# autonomiczny_odkurzacz_sch.net
KiCad netlist of a schematic drawn in Altium Designer
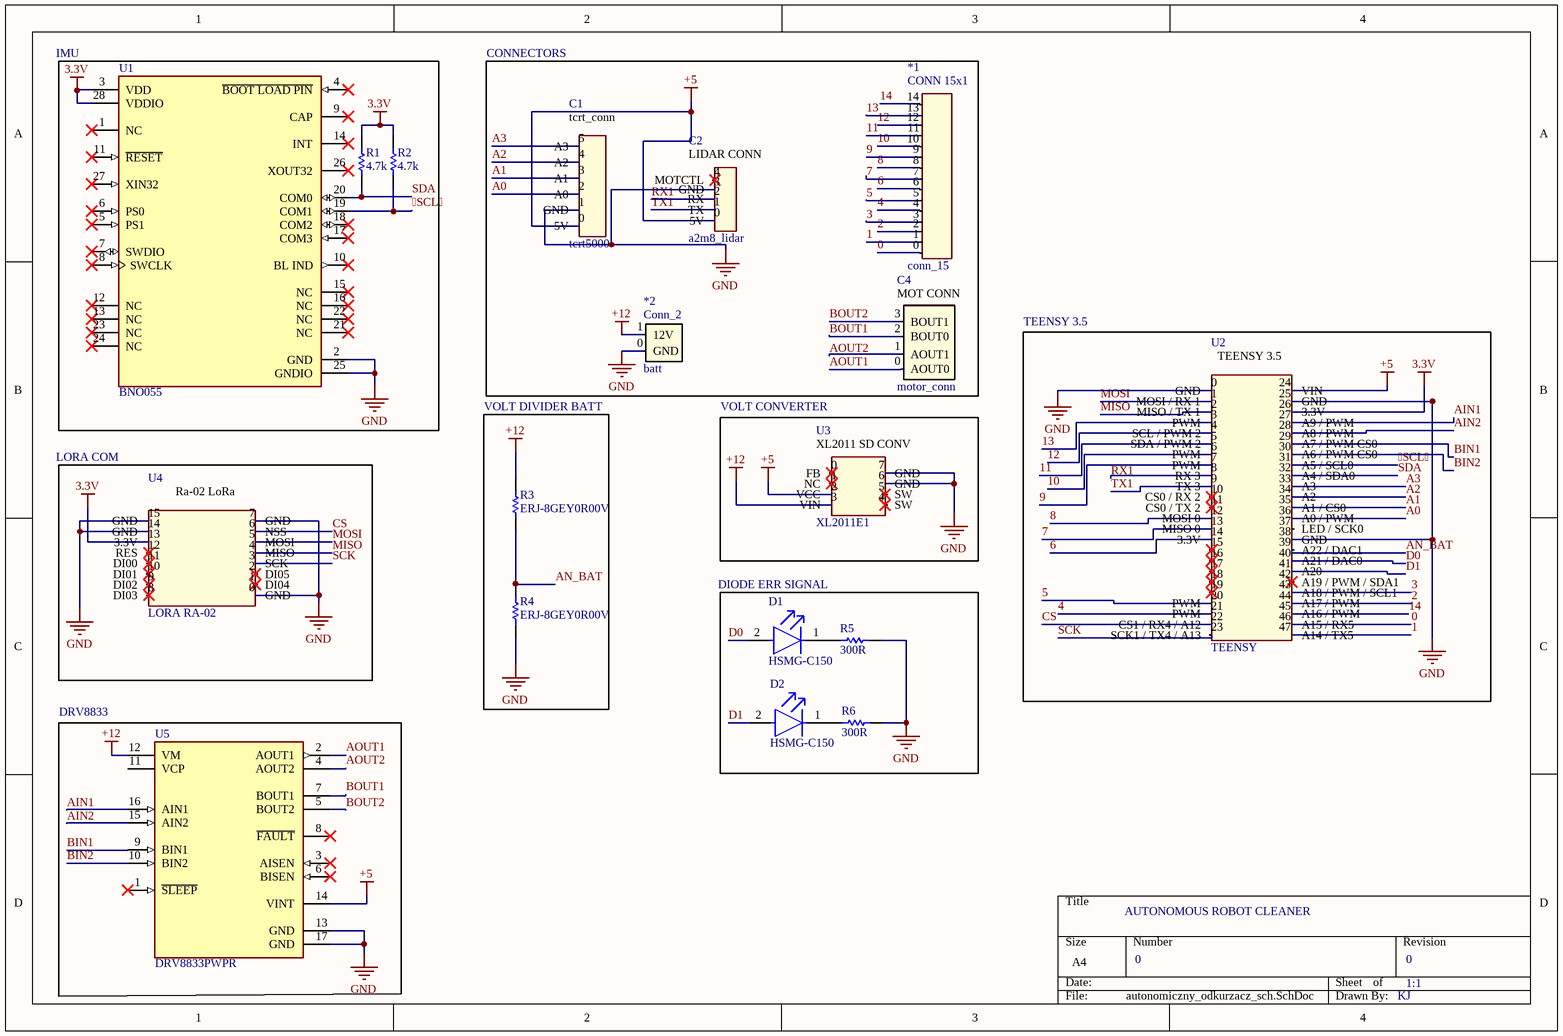
[diagram p0: autonomiczny_odkurzacz_sch.SchDoc]

(export (version "E")
  (design (tool "Eeschema 10.0.6"))
  (components
    (comp (ref "*1")
      (value "conn_15")
      (footprint "PCBComponent_1")
      (libsource (lib "workspace_kj_st") (part "conn_15"))
    )
    (comp (ref "*2") (value "batt") (footprint "conn_2:conn_2") (libsource (lib "MySchLib") (part "conn_2")))
    (comp (ref "C1")
      (value "tcrt5000")
      (footprint "PCBComponent_1")
      (libsource (lib "workspace_kj_st") (part "tcrt"))
    )
    (comp (ref "C2")
      (value "a2m8_lidar")
      (footprint "lidar_pcb:PCBComponent_1")
      (libsource (lib "MySchLib") (part "a2m8_lidar"))
    )
    (comp (ref "C4")
      (value "motor_conn")
      (footprint "PCBComponent_1")
      (libsource (lib "workspace_kj_st") (part "motor_conn"))
    )
    (comp (ref "D1")
      (value "HSMG-C150")
      (footprint "FP-HSMG-C150-MFG")
      (description "LED GREEN DIFFUSED 1206 SMD")
      (fields
        (field (name "MANUFACTURER") "Broadcom")
        (field (name "OCTOPART") "https://octopart.com/hsmg-c150-broadcom-71131304")
      )
      (libsource (lib "Altium Content Vault") (part "8706943c75ba83719d021d2fdc84c58"))
    )
    (comp (ref "D2")
      (value "HSMG-C150")
      (footprint "FP-HSMG-C150-MFG")
      (description "LED GREEN DIFFUSED 1206 SMD")
      (fields
        (field (name "MANUFACTURER") "Broadcom")
        (field (name "OCTOPART") "https://octopart.com/hsmg-c150-broadcom-71131304")
      )
      (libsource (lib "Altium Content Vault") (part "8706943c75ba83719d021d2fdc84c58"))
    )
    (comp (ref "R1")
      (value "4.7k")
      (footprint "RESC3216X70X50NL05T20")
      (fields (field (name "MANUFACTURER") "Panasonic") (field (name "PART NUMBER") "ERJ-8GEY0R00V"))
      (libsource (lib "Altium Content Vault") (part "RES"))
    )
    (comp (ref "R2")
      (value "4.7k")
      (footprint "RESC3216X70X50NL05T20")
      (fields (field (name "MANUFACTURER") "Panasonic") (field (name "PART NUMBER") "ERJ-8GEY0R00V"))
      (libsource (lib "Altium Content Vault") (part "RES"))
    )
    (comp (ref "R3")
      (value "ERJ-8GEY0R00V")
      (footprint "RESC3216X70X50NL05T20")
      (fields (field (name "MANUFACTURER") "Panasonic"))
      (libsource (lib "Altium Content Vault") (part "RES"))
    )
    (comp (ref "R4")
      (value "ERJ-8GEY0R00V")
      (footprint "RESC3216X70X50NL05T20")
      (fields (field (name "MANUFACTURER") "Panasonic"))
      (libsource (lib "Altium Content Vault") (part "RES"))
    )
    (comp (ref "R5")
      (value "300R")
      (footprint "RESC3216X70X50NL05T20")
      (fields (field (name "MANUFACTURER") "Panasonic") (field (name "PART NUMBER") "ERJ-8GEY0R00V"))
      (libsource (lib "Altium Content Vault") (part "RES"))
    )
    (comp (ref "R6")
      (value "300R")
      (footprint "RESC3216X70X50NL05T20")
      (fields (field (name "MANUFACTURER") "Panasonic") (field (name "PART NUMBER") "ERJ-8GEY0R00V"))
      (libsource (lib "Altium Content Vault") (part "RES"))
    )
    (comp (ref "U1")
      (value "BNO055")
      (footprint "FP-BNO055-MFG")
      (description "IMU ACCEL/GYRO/MAG I2C 28LGA")
      (libsource (lib "Altium Content Vault") (part "ba837af00a0b6167256f888b31462b1"))
    )
    (comp (ref "U2")
      (value "TEENSY")
      (footprint "PCBComponent_1")
      (libsource (lib "workspace_kj_st") (part "teensy_3_5"))
    )
    (comp (ref "U3")
      (value "XL2011E1")
      (footprint "PCBComponent_1")
      (libsource (lib "workspace_kj_st") (part "xl2011e1"))
    )
    (comp (ref "U4")
      (value "LORA RA-02")
      (footprint "lora_pcb:PCBComponent_1")
      (libsource (lib "MySchLib") (part "lora_ra02"))
    )
    (comp (ref "U5")
      (value "DRV8833PWPR")
      (footprint "FP-PWP0016C-IPC_A")
      (description "IC MOTOR DRIVER PAR 16HTSSOP")
      (libsource (lib "Altium Content Vault") (part "bca689d78e207bdabf30b9b31c2f798"))
    )
  )
  (nets
    (net (code "1") (name "+5") (class "Default")
      (node (ref "C1") (pin "0") (pinfunction "5V_0") (pintype "passive"))
      (node (ref "C2") (pin "0") (pinfunction "5V_0") (pintype "passive"))
      (node (ref "U2") (pin "24") (pinfunction "VIN_24") (pintype "passive"))
      (node (ref "U3") (pin "2") (pinfunction "VCC_2") (pintype "passive"))
      (node (ref "U5") (pin "14") (pinfunction "VINT_14") (pintype "power_in"))
    )
    (net (code "2") (name "+12") (class "Default")
      (node (ref "*2") (pin "1") (pinfunction "12V_1") (pintype "passive"))
      (node (ref "R3") (pin "2") (pinfunction "2_2") (pintype "passive"))
      (node (ref "U3") (pin "3") (pinfunction "VIN_3") (pintype "passive"))
      (node (ref "U5") (pin "12") (pinfunction "VM_12") (pintype "power_in"))
    )
    (net (code "3") (name "/SCL") (class "Default")
      (node (ref "R2") (pin "1") (pinfunction "1_1") (pintype "passive"))
      (node (ref "U1") (pin "19") (pinfunction "COM1_19") (pintype "bidirectional"))
      (node (ref "U2") (pin "31") (pinfunction "A5_/_SCL0_31") (pintype "passive"))
    )
    (net (code "4") (name "/0") (class "Default")
      (node (ref "*1") (pin "0") (pintype "passive"))
      (node (ref "U2") (pin "46") (pinfunction "A15_/_RX5_46") (pintype "passive"))
    )
    (net (code "5") (name "/1") (class "Default")
      (node (ref "*1") (pin "1") (pintype "passive"))
      (node (ref "U2") (pin "47") (pinfunction "A14_/_TX5_47") (pintype "passive"))
    )
    (net (code "6") (name "/2") (class "Default")
      (node (ref "*1") (pin "2") (pintype "passive"))
      (node (ref "U2") (pin "44") (pinfunction "A17_/_PWM_44") (pintype "passive"))
    )
    (net (code "7") (name "/3") (class "Default")
      (node (ref "*1") (pin "3") (pintype "passive"))
      (node (ref "U2") (pin "43") (pinfunction "A18_/_PWM_/_SCL1_43") (pintype "passive"))
    )
    (net (code "8") (name "/4") (class "Default")
      (node (ref "*1") (pin "4") (pintype "passive"))
      (node (ref "U2") (pin "21") (pinfunction "PWM_21") (pintype "passive"))
    )
    (net (code "9") (name "/5") (class "Default")
      (node (ref "*1") (pin "5") (pintype "passive"))
      (node (ref "U2") (pin "20") (pinfunction "PWM_20") (pintype "passive"))
    )
    (net (code "10") (name "/6") (class "Default")
      (node (ref "*1") (pin "6") (pintype "passive"))
      (node (ref "U2") (pin "14") (pinfunction "3.3V_14") (pintype "passive"))
    )
    (net (code "11") (name "/7") (class "Default")
      (node (ref "*1") (pin "7") (pintype "passive"))
      (node (ref "U2") (pin "13") (pinfunction "MISO_0_13") (pintype "passive"))
    )
    (net (code "12") (name "/8") (class "Default")
      (node (ref "*1") (pin "8") (pintype "passive"))
      (node (ref "U2") (pin "12") (pinfunction "MOSI_0_12") (pintype "passive"))
    )
    (net (code "13") (name "/9") (class "Default")
      (node (ref "*1") (pin "9") (pintype "passive"))
      (node (ref "U2") (pin "7") (pinfunction "PWM_7") (pintype "passive"))
    )
    (net (code "14") (name "/10") (class "Default")
      (node (ref "*1") (pin "10") (pintype "passive"))
      (node (ref "U2") (pin "6") (pinfunction "PWM_6") (pintype "passive"))
    )
    (net (code "15") (name "/11") (class "Default")
      (node (ref "*1") (pin "11") (pintype "passive"))
      (node (ref "U2") (pin "5") (pinfunction "SDA_/_PWM_2_5") (pintype "passive"))
    )
    (net (code "16") (name "/12") (class "Default")
      (node (ref "*1") (pin "12") (pintype "passive"))
      (node (ref "U2") (pin "4") (pinfunction "SCL_/_PWM_2_4") (pintype "passive"))
    )
    (net (code "17") (name "/13") (class "Default")
      (node (ref "*1") (pin "13") (pintype "passive"))
      (node (ref "U2") (pin "3") (pinfunction "PWM_3") (pintype "passive"))
    )
    (net (code "18") (name "/14") (class "Default")
      (node (ref "*1") (pin "14") (pintype "passive"))
      (node (ref "U2") (pin "45") (pinfunction "A16_/_PWM_45") (pintype "passive"))
    )
    (net (code "19") (name "/A0") (class "Default")
      (node (ref "C1") (pin "2") (pinfunction "A0_2") (pintype "passive"))
      (node (ref "U2") (pin "36") (pinfunction "A0_/_PWM_36") (pintype "passive"))
    )
    (net (code "20") (name "/A1") (class "Default")
      (node (ref "C1") (pin "3") (pinfunction "A1_3") (pintype "passive"))
      (node (ref "U2") (pin "35") (pinfunction "A1_/_CS0_35") (pintype "passive"))
    )
    (net (code "21") (name "/A2") (class "Default")
      (node (ref "C1") (pin "4") (pinfunction "A2_4") (pintype "passive"))
      (node (ref "U2") (pin "34") (pinfunction "A2_34") (pintype "passive"))
    )
    (net (code "22") (name "/A3") (class "Default")
      (node (ref "C1") (pin "5") (pinfunction "A3_5") (pintype "passive"))
      (node (ref "U2") (pin "33") (pinfunction "A3_33") (pintype "passive"))
    )
    (net (code "23") (name "/AIN1") (class "Default")
      (node (ref "U2") (pin "27") (pinfunction "A9_/_PWM_27") (pintype "passive"))
      (node (ref "U5") (pin "16") (pinfunction "AIN1_16") (pintype "input"))
    )
    (net (code "24") (name "/AIN2") (class "Default")
      (node (ref "U2") (pin "28") (pinfunction "A8_/_PWM_28") (pintype "passive"))
      (node (ref "U5") (pin "15") (pinfunction "AIN2_15") (pintype "input"))
    )
    (net (code "25") (name "/AN_BAT") (class "Default")
      (node (ref "R3") (pin "1") (pinfunction "1_1") (pintype "passive"))
      (node (ref "R4") (pin "2") (pinfunction "2_2") (pintype "passive"))
      (node (ref "U2") (pin "39") (pinfunction "A22_/_DAC1_39") (pintype "passive"))
    )
    (net (code "26") (name "/AOUT1") (class "Default")
      (node (ref "C4") (pin "0") (pinfunction "AOUT0_0") (pintype "passive"))
      (node (ref "U5") (pin "2") (pinfunction "AOUT1_2") (pintype "output"))
    )
    (net (code "27") (name "/AOUT2") (class "Default")
      (node (ref "C4") (pin "1") (pinfunction "AOUT1_1") (pintype "passive"))
      (node (ref "U5") (pin "4") (pinfunction "AOUT2_4") (pintype "tri_state"))
    )
    (net (code "28") (name "/BIN1") (class "Default")
      (node (ref "U2") (pin "29") (pinfunction "A7_/_PWM_CS0_29") (pintype "passive"))
      (node (ref "U5") (pin "9") (pinfunction "BIN1_9") (pintype "input"))
    )
    (net (code "29") (name "/BIN2") (class "Default")
      (node (ref "U2") (pin "30") (pinfunction "A6_/_PWM_CS0_30") (pintype "passive"))
      (node (ref "U5") (pin "10") (pinfunction "BIN2_10") (pintype "input"))
    )
    (net (code "30") (name "/BOUT1") (class "Default")
      (node (ref "C4") (pin "2") (pinfunction "BOUT0_2") (pintype "passive"))
      (node (ref "U5") (pin "7") (pinfunction "BOUT1_7") (pintype "tri_state"))
    )
    (net (code "31") (name "/BOUT2") (class "Default")
      (node (ref "C4") (pin "3") (pinfunction "BOUT1_3") (pintype "passive"))
      (node (ref "U5") (pin "5") (pinfunction "BOUT2_5") (pintype "tri_state"))
    )
    (net (code "32") (name "/CS") (class "Default")
      (node (ref "U2") (pin "22") (pinfunction "CS1_/_RX4_/_A12_22") (pintype "passive"))
      (node (ref "U4") (pin "6") (pinfunction "NSS_6") (pintype "passive"))
    )
    (net (code "33") (name "/D0") (class "Default")
      (node (ref "D1") (pin "2") (pinfunction "A_2") (pintype "passive"))
      (node (ref "U2") (pin "40") (pinfunction "A21_/_DAC0_40") (pintype "passive"))
    )
    (net (code "34") (name "/D1") (class "Default")
      (node (ref "D2") (pin "2") (pinfunction "A_2") (pintype "passive"))
      (node (ref "U2") (pin "41") (pinfunction "A20_41") (pintype "passive"))
    )
    (net (code "35") (name "/MISO") (class "Default")
      (node (ref "U2") (pin "2") (pinfunction "MISO_/_TX_1_2") (pintype "passive"))
      (node (ref "U4") (pin "4") (pinfunction "MISO_4") (pintype "passive"))
    )
    (net (code "36") (name "/MOSI") (class "Default")
      (node (ref "U2") (pin "1") (pinfunction "MOSI_/_RX_1_1") (pintype "passive"))
      (node (ref "U4") (pin "5") (pinfunction "MOSI_5") (pintype "passive"))
    )
    (net (code "37") (name "/RX1") (class "Default")
      (node (ref "C2") (pin "2") (pinfunction "RX_2") (pintype "passive"))
      (node (ref "U2") (pin "8") (pinfunction "RX_3_8") (pintype "passive"))
    )
    (net (code "38") (name "/SCK") (class "Default")
      (node (ref "U2") (pin "23") (pinfunction "SCK1_/_TX4_/_A13_23") (pintype "passive"))
      (node (ref "U4") (pin "3") (pinfunction "SCK_3") (pintype "passive"))
    )
    (net (code "39") (name "/SDA") (class "Default")
      (node (ref "R1") (pin "1") (pinfunction "1_1") (pintype "passive"))
      (node (ref "U1") (pin "20") (pinfunction "COM0_20") (pintype "bidirectional"))
      (node (ref "U2") (pin "32") (pinfunction "A4_/_SDA0_32") (pintype "passive"))
    )
    (net (code "40") (name "/TX1") (class "Default")
      (node (ref "C2") (pin "1") (pinfunction "TX_1") (pintype "passive"))
      (node (ref "U2") (pin "9") (pinfunction "TX_3_9") (pintype "passive"))
    )
    (net (code "41") (name "3.3V") (class "Default")
      (node (ref "R1") (pin "2") (pinfunction "2_2") (pintype "passive"))
      (node (ref "R2") (pin "2") (pinfunction "2_2") (pintype "passive"))
      (node (ref "U1") (pin "28") (pinfunction "VDDIO_28") (pintype "power_in"))
      (node (ref "U1") (pin "3") (pinfunction "VDD_3") (pintype "power_in"))
      (node (ref "U2") (pin "26") (pinfunction "3.3V_26") (pintype "passive"))
      (node (ref "U4") (pin "13") (pinfunction "3.3V_13") (pintype "passive"))
    )
    (net (code "42") (name "GND") (class "Default")
      (node (ref "*2") (pin "0") (pinfunction "GND_0") (pintype "passive"))
      (node (ref "C1") (pin "1") (pinfunction "GND_1") (pintype "passive"))
      (node (ref "C2") (pin "3") (pinfunction "GND_3") (pintype "passive"))
      (node (ref "R4") (pin "1") (pinfunction "1_1") (pintype "passive"))
      (node (ref "R5") (pin "2") (pinfunction "2_2") (pintype "passive"))
      (node (ref "R6") (pin "2") (pinfunction "2_2") (pintype "passive"))
      (node (ref "U1") (pin "2") (pinfunction "GND_2") (pintype "power_in"))
      (node (ref "U1") (pin "25") (pinfunction "GNDIO_25") (pintype "power_in"))
      (node (ref "U2") (pin "0") (pinfunction "GND_0") (pintype "passive"))
      (node (ref "U2") (pin "25") (pinfunction "GND_25") (pintype "passive"))
      (node (ref "U2") (pin "38") (pinfunction "GND_38") (pintype "passive"))
      (node (ref "U3") (pin "6") (pinfunction "GND_6") (pintype "passive"))
      (node (ref "U3") (pin "7") (pinfunction "GND_7") (pintype "passive"))
      (node (ref "U4") (pin "0") (pinfunction "GND_0") (pintype "passive"))
      (node (ref "U4") (pin "14") (pinfunction "GND_14") (pintype "passive"))
      (node (ref "U4") (pin "15") (pinfunction "GND_15") (pintype "passive"))
      (node (ref "U4") (pin "7") (pinfunction "GND_7") (pintype "passive"))
      (node (ref "U5") (pin "13") (pinfunction "GND_13") (pintype "power_in"))
      (node (ref "U5") (pin "17") (pinfunction "GND_17") (pintype "power_in"))
    )
    (net (code "43") (name "Net-(D1-C)") (class "Default")
      (node (ref "D1") (pin "1") (pinfunction "C_1") (pintype "passive"))
      (node (ref "R5") (pin "1") (pinfunction "1_1") (pintype "passive"))
    )
    (net (code "44") (name "Net-(D2-C)") (class "Default")
      (node (ref "D2") (pin "1") (pinfunction "C_1") (pintype "passive"))
      (node (ref "R6") (pin "1") (pinfunction "1_1") (pintype "passive"))
    )
    (net (code "45") (name "unconnected-(C2-MOTCTL-Pad4)") (class "Default")
      (node (ref "C2") (pin "4") (pinfunction "MOTCTL_4") (pintype "passive+no_connect"))
    )
    (net (code "46") (name "unconnected-(U1-BL_IND-Pad10)") (class "Default")
      (node (ref "U1") (pin "10") (pinfunction "BL_IND_10") (pintype "output+no_connect"))
    )
    (net (code "47") (name "unconnected-(U1-CAP-Pad9)") (class "Default")
      (node (ref "U1") (pin "9") (pinfunction "CAP_9") (pintype "passive+no_connect"))
    )
    (net (code "48") (name "unconnected-(U1-COM2-Pad18)") (class "Default")
      (node (ref "U1") (pin "18") (pinfunction "COM2_18") (pintype "bidirectional+no_connect"))
    )
    (net (code "49") (name "unconnected-(U1-COM3-Pad17)") (class "Default")
      (node (ref "U1") (pin "17") (pinfunction "COM3_17") (pintype "input+no_connect"))
    )
    (net (code "50") (name "unconnected-(U1-INT-Pad14)") (class "Default")
      (node (ref "U1") (pin "14") (pinfunction "INT_14") (pintype "passive+no_connect"))
    )
    (net (code "51") (name "unconnected-(U1-NC-Pad1)") (class "Default")
      (node (ref "U1") (pin "1") (pinfunction "NC_1") (pintype "passive+no_connect"))
    )
    (net (code "52") (name "unconnected-(U1-NC-Pad12)") (class "Default")
      (node (ref "U1") (pin "12") (pinfunction "NC_12") (pintype "passive+no_connect"))
    )
    (net (code "53") (name "unconnected-(U1-NC-Pad13)") (class "Default")
      (node (ref "U1") (pin "13") (pinfunction "NC_13") (pintype "passive+no_connect"))
    )
    (net (code "54") (name "unconnected-(U1-NC-Pad15)") (class "Default")
      (node (ref "U1") (pin "15") (pinfunction "NC_15") (pintype "passive+no_connect"))
    )
    (net (code "55") (name "unconnected-(U1-NC-Pad16)") (class "Default")
      (node (ref "U1") (pin "16") (pinfunction "NC_16") (pintype "passive+no_connect"))
    )
    (net (code "56") (name "unconnected-(U1-NC-Pad21)") (class "Default")
      (node (ref "U1") (pin "21") (pinfunction "NC_21") (pintype "passive+no_connect"))
    )
    (net (code "57") (name "unconnected-(U1-NC-Pad22)") (class "Default")
      (node (ref "U1") (pin "22") (pinfunction "NC_22") (pintype "passive+no_connect"))
    )
    (net (code "58") (name "unconnected-(U1-NC-Pad23)") (class "Default")
      (node (ref "U1") (pin "23") (pinfunction "NC_23") (pintype "passive+no_connect"))
    )
    (net (code "59") (name "unconnected-(U1-NC-Pad24)") (class "Default")
      (node (ref "U1") (pin "24") (pinfunction "NC_24") (pintype "passive+no_connect"))
    )
    (net (code "60") (name "unconnected-(U1-PS0-Pad6)") (class "Default")
      (node (ref "U1") (pin "6") (pinfunction "PS0_6") (pintype "input+no_connect"))
    )
    (net (code "61") (name "unconnected-(U1-PS1-Pad5)") (class "Default")
      (node (ref "U1") (pin "5") (pinfunction "PS1_5") (pintype "input+no_connect"))
    )
    (net (code "62") (name "unconnected-(U1-SWCLK-Pad8)") (class "Default")
      (node (ref "U1") (pin "8") (pinfunction "SWCLK_8") (pintype "input+no_connect"))
    )
    (net (code "63") (name "unconnected-(U1-SWDIO-Pad7)") (class "Default")
      (node (ref "U1") (pin "7") (pinfunction "SWDIO_7") (pintype "bidirectional+no_connect"))
    )
    (net (code "64") (name "unconnected-(U1-XIN32-Pad27)") (class "Default")
      (node (ref "U1") (pin "27") (pinfunction "XIN32_27") (pintype "input+no_connect"))
    )
    (net (code "65") (name "unconnected-(U1-XOUT32-Pad26)") (class "Default")
      (node (ref "U1") (pin "26") (pinfunction "XOUT32_26") (pintype "passive+no_connect"))
    )
    (net (code "66") (name "unconnected-(U1-~{BOOT_LOAD_PIN}-Pad4)") (class "Default")
      (node (ref "U1") (pin "4") (pinfunction "~{BOOT_LOAD_PIN}_4") (pintype "input+no_connect"))
    )
    (net (code "67") (name "unconnected-(U1-~{RESET}-Pad11)") (class "Default")
      (node (ref "U1") (pin "11") (pinfunction "~{RESET}_11") (pintype "input+no_connect"))
    )
    (net (code "68") (name "unconnected-(U2-A19_{slash}_PWM_{slash}_SDA1-Pad42)") (class "Default")
      (node (ref "U2") (pin "42") (pinfunction "A19_/_PWM_/_SDA1_42") (pintype "passive+no_connect"))
    )
    (net (code "69") (name "unconnected-(U2-CS0_{slash}_RX_2-Pad10)") (class "Default")
      (node (ref "U2") (pin "10") (pinfunction "CS0_/_RX_2_10") (pintype "passive+no_connect"))
    )
    (net (code "70") (name "unconnected-(U2-CS0_{slash}_TX_2-Pad11)") (class "Default")
      (node (ref "U2") (pin "11") (pinfunction "CS0_/_TX_2_11") (pintype "passive+no_connect"))
    )
    (net (code "71") (name "unconnected-(U2-LED_{slash}_SCK0-Pad37)") (class "Default")
      (node (ref "U2") (pin "37") (pinfunction "LED_/_SCK0_37") (pintype "passive"))
    )
    (net (code "72") (name "unconnected-(U2-Pad15)") (class "Default")
      (node (ref "U2") (pin "15") (pintype "passive+no_connect"))
    )
    (net (code "73") (name "unconnected-(U2-Pad16)") (class "Default")
      (node (ref "U2") (pin "16") (pintype "passive+no_connect"))
    )
    (net (code "74") (name "unconnected-(U2-Pad17)") (class "Default")
      (node (ref "U2") (pin "17") (pintype "passive+no_connect"))
    )
    (net (code "75") (name "unconnected-(U2-Pad18)") (class "Default")
      (node (ref "U2") (pin "18") (pintype "passive+no_connect"))
    )
    (net (code "76") (name "unconnected-(U2-Pad19)") (class "Default")
      (node (ref "U2") (pin "19") (pintype "passive+no_connect"))
    )
    (net (code "77") (name "unconnected-(U3-FB-Pad0)") (class "Default")
      (node (ref "U3") (pin "0") (pinfunction "FB_0") (pintype "passive+no_connect"))
    )
    (net (code "78") (name "unconnected-(U3-NC-Pad1)") (class "Default")
      (node (ref "U3") (pin "1") (pinfunction "NC_1") (pintype "passive+no_connect"))
    )
    (net (code "79") (name "unconnected-(U3-SW-Pad4)") (class "Default")
      (node (ref "U3") (pin "4") (pinfunction "SW_4") (pintype "passive+no_connect"))
    )
    (net (code "80") (name "unconnected-(U3-SW-Pad5)") (class "Default")
      (node (ref "U3") (pin "5") (pinfunction "SW_5") (pintype "passive+no_connect"))
    )
    (net (code "81") (name "unconnected-(U4-DI00-Pad11)") (class "Default")
      (node (ref "U4") (pin "11") (pinfunction "DI00_11") (pintype "passive+no_connect"))
    )
    (net (code "82") (name "unconnected-(U4-DI01-Pad10)") (class "Default")
      (node (ref "U4") (pin "10") (pinfunction "DI01_10") (pintype "passive+no_connect"))
    )
    (net (code "83") (name "unconnected-(U4-DI02-Pad9)") (class "Default")
      (node (ref "U4") (pin "9") (pinfunction "DI02_9") (pintype "passive+no_connect"))
    )
    (net (code "84") (name "unconnected-(U4-DI03-Pad8)") (class "Default")
      (node (ref "U4") (pin "8") (pinfunction "DI03_8") (pintype "passive+no_connect"))
    )
    (net (code "85") (name "unconnected-(U4-DI04-Pad1)") (class "Default")
      (node (ref "U4") (pin "1") (pinfunction "DI04_1") (pintype "passive+no_connect"))
    )
    (net (code "86") (name "unconnected-(U4-DI05-Pad2)") (class "Default")
      (node (ref "U4") (pin "2") (pinfunction "DI05_2") (pintype "passive+no_connect"))
    )
    (net (code "87") (name "unconnected-(U4-RES-Pad12)") (class "Default")
      (node (ref "U4") (pin "12") (pinfunction "RES_12") (pintype "passive+no_connect"))
    )
    (net (code "88") (name "unconnected-(U5-AISEN-Pad3)") (class "Default")
      (node (ref "U5") (pin "3") (pinfunction "AISEN_3") (pintype "input+no_connect"))
    )
    (net (code "89") (name "unconnected-(U5-BISEN-Pad6)") (class "Default")
      (node (ref "U5") (pin "6") (pinfunction "BISEN_6") (pintype "input+no_connect"))
    )
    (net (code "90") (name "unconnected-(U5-VCP-Pad11)") (class "Default")
      (node (ref "U5") (pin "11") (pinfunction "VCP_11") (pintype "passive"))
    )
    (net (code "91") (name "unconnected-(U5-~{FAULT}-Pad8)") (class "Default")
      (node (ref "U5") (pin "8") (pinfunction "~{FAULT}_8") (pintype "open_collector+no_connect"))
    )
    (net (code "92") (name "unconnected-(U5-~{SLEEP}-Pad1)") (class "Default")
      (node (ref "U5") (pin "1") (pinfunction "~{SLEEP}_1") (pintype "input+no_connect"))
    )
  )
)
